# xmc.net
KiCad netlist of a schematic drawn in EAGLE
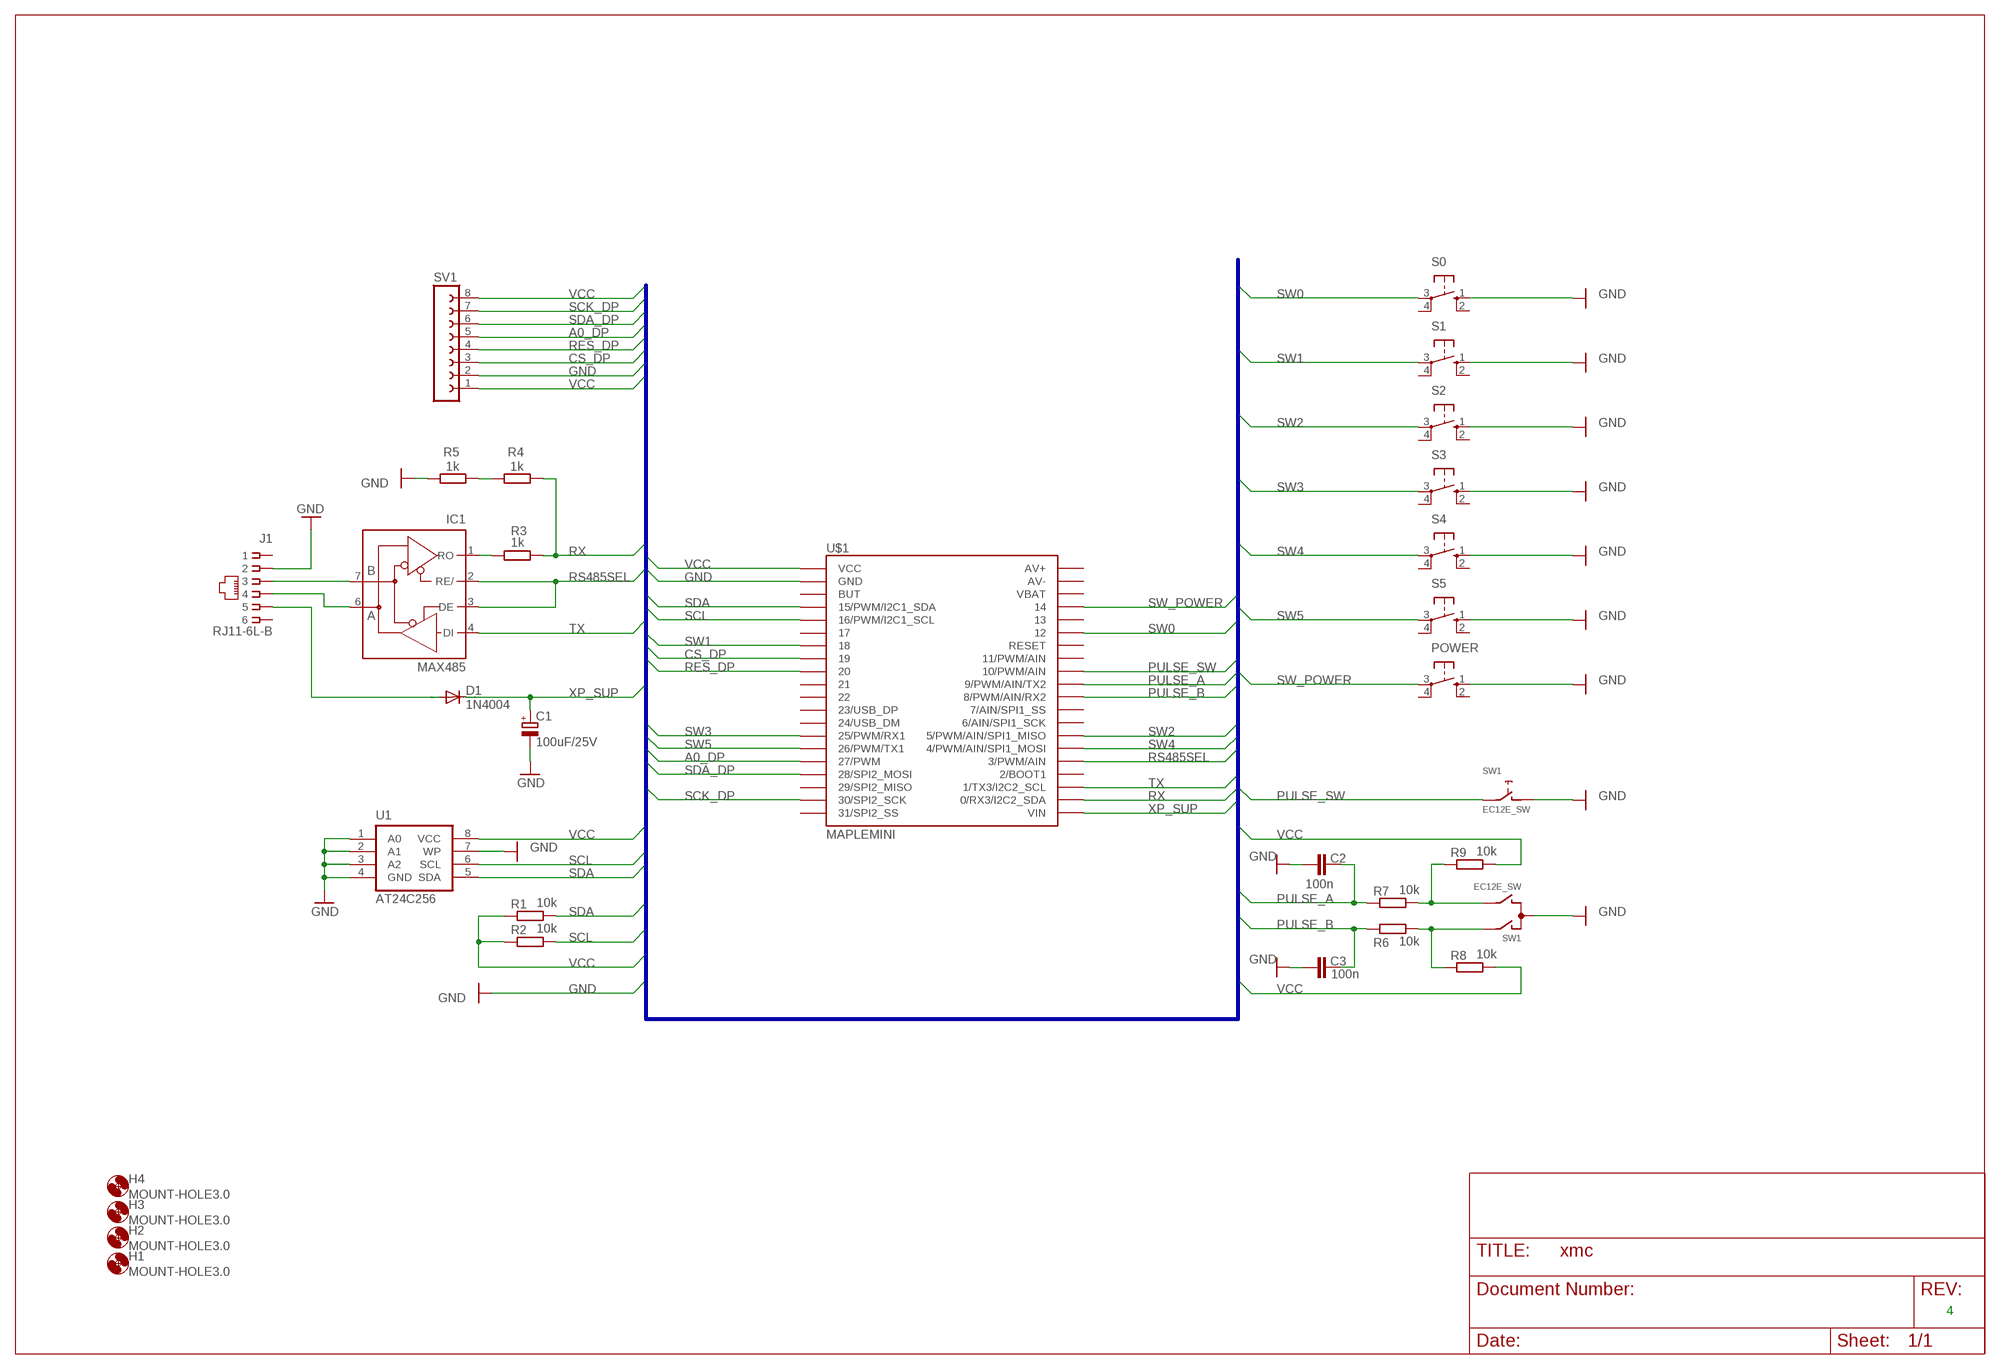
[diagram p0: schematic, sheet 1]

(export (version "E")
  (design (tool "Eeschema 10.0.6"))
  (components
    (comp (ref "C1")
      (value "100uF/25V")
      (footprint "eagle-import:E2,5-6")
      (libsource (lib "eagle-import") (part "CPOL-EUE2.5-6"))
    )
    (comp (ref "C2")
      (value "100n")
      (footprint "eagle-import:C025-024X044")
      (libsource (lib "eagle-import") (part "C-EU025-024X044"))
    )
    (comp (ref "C3")
      (value "100n")
      (footprint "eagle-import:C025-024X044")
      (libsource (lib "eagle-import") (part "C-EU025-024X044"))
    )
    (comp (ref "D1")
      (value "1N4004")
      (footprint "eagle-import:DO41-10")
      (libsource (lib "eagle-import") (part "1N4004"))
    )
    (comp (ref "H1")
      (value "MOUNT-HOLE3.0")
      (footprint "eagle-import:3,0")
      (libsource (lib "eagle-import") (part "MOUNT-HOLE3.0"))
    )
    (comp (ref "H2")
      (value "MOUNT-HOLE3.0")
      (footprint "eagle-import:3,0")
      (libsource (lib "eagle-import") (part "MOUNT-HOLE3.0"))
    )
    (comp (ref "H3")
      (value "MOUNT-HOLE3.0")
      (footprint "eagle-import:3,0")
      (libsource (lib "eagle-import") (part "MOUNT-HOLE3.0"))
    )
    (comp (ref "H4")
      (value "MOUNT-HOLE3.0")
      (footprint "eagle-import:3,0")
      (libsource (lib "eagle-import") (part "MOUNT-HOLE3.0"))
    )
    (comp (ref "IC1")
      (value "MAX485")
      (footprint "eagle-import:SO08")
      (fields (field (name "MF") "MAXIM") (field (name "MPN") "MAX481CSA"))
      (libsource (lib "eagle-import") (part "MAX481CSA"))
    )
    (comp (ref "J1")
      (value "RJ11-6L-B")
      (footprint "eagle-import:RJ11-NO_SHIELD")
      (fields (field (name "MF") "TYCO ELECTRONICS"))
      (libsource (lib "eagle-import") (part "RJ11-6L-B"))
    )
    (comp (ref "POWER")
      (value "10-XX")
      (footprint "eagle-import:B3F-10XX")
      (fields (field (name "MPN") "B3F-1000"))
      (libsource (lib "eagle-import") (part "10-XX"))
    )
    (comp (ref "R1")
      (value "10k")
      (footprint "eagle-import:0207_7")
      (libsource (lib "eagle-import") (part "R-EU_0207/7"))
    )
    (comp (ref "R2")
      (value "10k")
      (footprint "eagle-import:0207_7")
      (libsource (lib "eagle-import") (part "R-EU_0207/7"))
    )
    (comp (ref "R3")
      (value "1k")
      (footprint "eagle-import:0207_7")
      (libsource (lib "eagle-import") (part "R-EU_0207/7"))
    )
    (comp (ref "R4")
      (value "1k")
      (footprint "eagle-import:0207_7")
      (libsource (lib "eagle-import") (part "R-EU_0207/7"))
    )
    (comp (ref "R5")
      (value "1k")
      (footprint "eagle-import:0207_7")
      (libsource (lib "eagle-import") (part "R-EU_0207/7"))
    )
    (comp (ref "R6")
      (value "10k")
      (footprint "eagle-import:0207_7")
      (libsource (lib "eagle-import") (part "R-EU_0207/7"))
    )
    (comp (ref "R7")
      (value "10k")
      (footprint "eagle-import:0207_7")
      (libsource (lib "eagle-import") (part "R-EU_0207/7"))
    )
    (comp (ref "R8")
      (value "10k")
      (footprint "eagle-import:0207_7")
      (libsource (lib "eagle-import") (part "R-EU_0207/7"))
    )
    (comp (ref "R9")
      (value "10k")
      (footprint "eagle-import:0207_7")
      (libsource (lib "eagle-import") (part "R-EU_0207/7"))
    )
    (comp (ref "S0")
      (value "10-XX")
      (footprint "eagle-import:B3F-10XX")
      (fields (field (name "MPN") "B3F-1000"))
      (libsource (lib "eagle-import") (part "10-XX"))
    )
    (comp (ref "S1")
      (value "10-XX")
      (footprint "eagle-import:B3F-10XX")
      (fields (field (name "MPN") "B3F-1000"))
      (libsource (lib "eagle-import") (part "10-XX"))
    )
    (comp (ref "S2")
      (value "10-XX")
      (footprint "eagle-import:B3F-10XX")
      (fields (field (name "MPN") "B3F-1000"))
      (libsource (lib "eagle-import") (part "10-XX"))
    )
    (comp (ref "S3")
      (value "10-XX")
      (footprint "eagle-import:B3F-10XX")
      (fields (field (name "MPN") "B3F-1000"))
      (libsource (lib "eagle-import") (part "10-XX"))
    )
    (comp (ref "S4")
      (value "10-XX")
      (footprint "eagle-import:B3F-10XX")
      (fields (field (name "MPN") "B3F-1000"))
      (libsource (lib "eagle-import") (part "10-XX"))
    )
    (comp (ref "S5")
      (value "10-XX")
      (footprint "eagle-import:B3F-10XX")
      (fields (field (name "MPN") "B3F-1000"))
      (libsource (lib "eagle-import") (part "10-XX"))
    )
    (comp (ref "SV1")
      (value "FE08-1")
      (footprint "eagle-import:FE08")
      (libsource (lib "eagle-import") (part "FE08-1"))
    )
    (comp (ref "SW1")
      (value "EC12E_SW")
      (footprint "eagle-import:ALPS_EC12E_SW")
      (fields (field (name "MPN") "EC12E2424407"))
      (libsource (lib "eagle-import") (part "EC12E_SW"))
    )
    (comp (ref "U$1")
      (value "MAPLEMINI")
      (footprint "eagle-import:20-DIP")
      (libsource (lib "eagle-import") (part "MAPLEMINI"))
    )
    (comp (ref "U1")
      (value "AT24C256")
      (footprint "eagle-import:SO08-8S1")
      (libsource (lib "eagle-import") (part "AT24CXX"))
    )
  )
  (nets
    (net (code "1") (name "/A0_DP") (class "Default")
      (node (ref "SV1") (pin "5") (pinfunction "5_5") (pintype "passive"))
      (node (ref "U$1") (pin "16") (pinfunction "27/PWM_16") (pintype "bidirectional"))
    )
    (net (code "2") (name "/CS_DP") (class "Default")
      (node (ref "SV1") (pin "3") (pinfunction "3_3") (pintype "passive"))
      (node (ref "U$1") (pin "8") (pinfunction "19_8") (pintype "bidirectional"))
    )
    (net (code "3") (name "/PULSE_A") (class "Default")
      (node (ref "C2") (pin "1") (pinfunction "1_1") (pintype "passive"))
      (node (ref "R7") (pin "1") (pinfunction "1_1") (pintype "passive"))
      (node (ref "U$1") (pin "31") (pinfunction "9/PWM/AIN/TX2_31") (pintype "bidirectional"))
    )
    (net (code "4") (name "/PULSE_B") (class "Default")
      (node (ref "C3") (pin "1") (pinfunction "1_1") (pintype "passive"))
      (node (ref "R6") (pin "1") (pinfunction "1_1") (pintype "passive"))
      (node (ref "U$1") (pin "30") (pinfunction "8/PWM/AIN/RX2_30") (pintype "bidirectional"))
    )
    (net (code "5") (name "/PULSE_SW") (class "Default")
      (node (ref "SW1") (pin "E") (pinfunction "2_E") (pintype "passive"))
      (node (ref "U$1") (pin "32") (pinfunction "10/PWM/AIN_32") (pintype "bidirectional"))
    )
    (net (code "6") (name "/RES_DP") (class "Default")
      (node (ref "SV1") (pin "4") (pinfunction "4_4") (pintype "passive"))
      (node (ref "U$1") (pin "9") (pinfunction "20_9") (pintype "bidirectional"))
    )
    (net (code "7") (name "/RS485SEL") (class "Default")
      (node (ref "IC1") (pin "2") (pinfunction "RE/_2") (pintype "input"))
      (node (ref "IC1") (pin "3") (pinfunction "DE_3") (pintype "input"))
      (node (ref "U$1") (pin "25") (pinfunction "3/PWM/AIN_25") (pintype "bidirectional"))
    )
    (net (code "8") (name "/RX") (class "Default")
      (node (ref "R3") (pin "2") (pinfunction "2_2") (pintype "passive"))
      (node (ref "R4") (pin "1") (pinfunction "1_1") (pintype "passive"))
      (node (ref "U$1") (pin "22") (pinfunction "0/RX3/I2C2_SDA_22") (pintype "bidirectional"))
    )
    (net (code "9") (name "/SCK_DP") (class "Default")
      (node (ref "SV1") (pin "7") (pinfunction "7_7") (pintype "passive"))
      (node (ref "U$1") (pin "19") (pinfunction "30/SPI2_SCK_19") (pintype "bidirectional"))
    )
    (net (code "10") (name "/SCL") (class "Default")
      (node (ref "R2") (pin "2") (pinfunction "2_2") (pintype "passive"))
      (node (ref "U$1") (pin "5") (pinfunction "16/PWM/I2C1_SCL_5") (pintype "bidirectional"))
      (node (ref "U1") (pin "6") (pinfunction "SCL_6") (pintype "bidirectional"))
    )
    (net (code "11") (name "/SDA") (class "Default")
      (node (ref "R1") (pin "2") (pinfunction "2_2") (pintype "passive"))
      (node (ref "U$1") (pin "4") (pinfunction "15/PWM/I2C1_SDA_4") (pintype "bidirectional"))
      (node (ref "U1") (pin "5") (pinfunction "SDA_5") (pintype "bidirectional"))
    )
    (net (code "12") (name "/SDA_DP") (class "Default")
      (node (ref "SV1") (pin "6") (pinfunction "6_6") (pintype "passive"))
      (node (ref "U$1") (pin "17") (pinfunction "28/SPI2_MOSI_17") (pintype "bidirectional"))
    )
    (net (code "13") (name "/SW0") (class "Default")
      (node (ref "S0") (pin "3") (pinfunction "P_3") (pintype "passive"))
      (node (ref "U$1") (pin "35") (pinfunction "12_35") (pintype "bidirectional"))
    )
    (net (code "14") (name "/SW1") (class "Default")
      (node (ref "S1") (pin "3") (pinfunction "P_3") (pintype "passive"))
      (node (ref "U$1") (pin "7") (pinfunction "18_7") (pintype "bidirectional"))
    )
    (net (code "15") (name "/SW2") (class "Default")
      (node (ref "S2") (pin "3") (pinfunction "P_3") (pintype "passive"))
      (node (ref "U$1") (pin "27") (pinfunction "5/PWM/AIN/SPI1_MISO_27") (pintype "bidirectional"))
    )
    (net (code "16") (name "/SW3") (class "Default")
      (node (ref "S3") (pin "3") (pinfunction "P_3") (pintype "passive"))
      (node (ref "U$1") (pin "14") (pinfunction "25/PWM/RX1_14") (pintype "bidirectional"))
    )
    (net (code "17") (name "/SW4") (class "Default")
      (node (ref "S4") (pin "3") (pinfunction "P_3") (pintype "passive"))
      (node (ref "U$1") (pin "26") (pinfunction "4/PWM/AIN/SPI1_MOSI_26") (pintype "bidirectional"))
    )
    (net (code "18") (name "/SW5") (class "Default")
      (node (ref "S5") (pin "3") (pinfunction "P_3") (pintype "passive"))
      (node (ref "U$1") (pin "15") (pinfunction "26/PWM/TX1_15") (pintype "bidirectional"))
    )
    (net (code "19") (name "/SW_POWER") (class "Default")
      (node (ref "POWER") (pin "3") (pinfunction "P_3") (pintype "passive"))
      (node (ref "U$1") (pin "37") (pinfunction "14_37") (pintype "bidirectional"))
    )
    (net (code "20") (name "/TX") (class "Default")
      (node (ref "IC1") (pin "4") (pinfunction "DI_4") (pintype "input"))
      (node (ref "U$1") (pin "23") (pinfunction "1/TX3/I2C2_SCL_23") (pintype "bidirectional"))
    )
    (net (code "21") (name "/VCC") (class "Default")
      (node (ref "R1") (pin "1") (pinfunction "1_1") (pintype "passive"))
      (node (ref "R2") (pin "1") (pinfunction "1_1") (pintype "passive"))
      (node (ref "R8") (pin "2") (pinfunction "2_2") (pintype "passive"))
      (node (ref "R9") (pin "2") (pinfunction "2_2") (pintype "passive"))
      (node (ref "SV1") (pin "1") (pinfunction "1_1") (pintype "passive"))
      (node (ref "SV1") (pin "8") (pinfunction "8_8") (pintype "passive"))
      (node (ref "U$1") (pin "1") (pinfunction "VCC_1") (pintype "bidirectional"))
      (node (ref "U1") (pin "8") (pinfunction "VCC_8") (pintype "power_in"))
    )
    (net (code "22") (name "/XP_SUP") (class "Default")
      (node (ref "C1") (pin "+") (pinfunction "+_+") (pintype "passive"))
      (node (ref "D1") (pin "C") (pinfunction "C_C") (pintype "passive"))
      (node (ref "U$1") (pin "21") (pinfunction "VIN_21") (pintype "bidirectional"))
    )
    (net (code "23") (name "GND") (class "Default")
      (node (ref "C1") (pin "-") (pinfunction "-_-") (pintype "passive"))
      (node (ref "C2") (pin "2") (pinfunction "2_2") (pintype "passive"))
      (node (ref "C3") (pin "2") (pinfunction "2_2") (pintype "passive"))
      (node (ref "J1") (pin "2") (pinfunction "2_2") (pintype "passive"))
      (node (ref "POWER") (pin "1") (pinfunction "S_1") (pintype "passive"))
      (node (ref "R5") (pin "2") (pinfunction "2_2") (pintype "passive"))
      (node (ref "S0") (pin "1") (pinfunction "S_1") (pintype "passive"))
      (node (ref "S1") (pin "1") (pinfunction "S_1") (pintype "passive"))
      (node (ref "S2") (pin "1") (pinfunction "S_1") (pintype "passive"))
      (node (ref "S3") (pin "1") (pinfunction "S_1") (pintype "passive"))
      (node (ref "S4") (pin "1") (pinfunction "S_1") (pintype "passive"))
      (node (ref "S5") (pin "1") (pinfunction "S_1") (pintype "passive"))
      (node (ref "SV1") (pin "2") (pinfunction "2_2") (pintype "passive"))
      (node (ref "SW1") (pin "C") (pinfunction "C_C") (pintype "passive"))
      (node (ref "SW1") (pin "D") (pinfunction "1_D") (pintype "passive"))
      (node (ref "U$1") (pin "2") (pinfunction "GND_2") (pintype "bidirectional"))
      (node (ref "U1") (pin "1") (pinfunction "A0_1") (pintype "input"))
      (node (ref "U1") (pin "2") (pinfunction "A1_2") (pintype "input"))
      (node (ref "U1") (pin "3") (pinfunction "A2_3") (pintype "input"))
      (node (ref "U1") (pin "4") (pinfunction "GND_4") (pintype "power_in"))
      (node (ref "U1") (pin "7") (pinfunction "WP_7") (pintype "bidirectional"))
    )
    (net (code "24") (name "Net-(D1-PadA)") (class "Default")
      (node (ref "D1") (pin "A") (pinfunction "A_A") (pintype "passive"))
      (node (ref "J1") (pin "5") (pinfunction "5_5") (pintype "passive"))
    )
    (net (code "25") (name "Net-(IC1A-A)") (class "Default")
      (node (ref "IC1") (pin "6") (pinfunction "A_6") (pintype "passive"))
      (node (ref "J1") (pin "4") (pinfunction "4_4") (pintype "passive"))
    )
    (net (code "26") (name "Net-(IC1A-B)") (class "Default")
      (node (ref "IC1") (pin "7") (pinfunction "B_7") (pintype "passive"))
      (node (ref "J1") (pin "3") (pinfunction "3_3") (pintype "passive"))
    )
    (net (code "27") (name "Net-(IC1A-RO)") (class "Default")
      (node (ref "IC1") (pin "1") (pinfunction "RO_1") (pintype "output"))
      (node (ref "R3") (pin "1") (pinfunction "1_1") (pintype "passive"))
    )
    (net (code "28") (name "Net-(R4-Pad2)") (class "Default")
      (node (ref "R4") (pin "2") (pinfunction "2_2") (pintype "passive"))
      (node (ref "R5") (pin "1") (pinfunction "1_1") (pintype "passive"))
    )
    (net (code "29") (name "Net-(R6-Pad2)") (class "Default")
      (node (ref "R6") (pin "2") (pinfunction "2_2") (pintype "passive"))
      (node (ref "R8") (pin "1") (pinfunction "1_1") (pintype "passive"))
      (node (ref "SW1") (pin "A") (pinfunction "A_A") (pintype "passive"))
    )
    (net (code "30") (name "Net-(R7-Pad2)") (class "Default")
      (node (ref "R7") (pin "2") (pinfunction "2_2") (pintype "passive"))
      (node (ref "R9") (pin "1") (pinfunction "1_1") (pintype "passive"))
      (node (ref "SW1") (pin "B") (pinfunction "B_B") (pintype "passive"))
    )
    (net (code "31") (name "unconnected-(J1-Pad1)") (class "Default")
      (node (ref "J1") (pin "1") (pinfunction "1_1") (pintype "passive"))
    )
    (net (code "32") (name "unconnected-(J1-Pad6)") (class "Default")
      (node (ref "J1") (pin "6") (pinfunction "6_6") (pintype "passive"))
    )
    (net (code "33") (name "unconnected-(POWER-P1-Pad4)") (class "Default")
      (node (ref "POWER") (pin "4") (pinfunction "P1_4") (pintype "passive"))
    )
    (net (code "34") (name "unconnected-(POWER-S1-Pad2)") (class "Default")
      (node (ref "POWER") (pin "2") (pinfunction "S1_2") (pintype "passive"))
    )
    (net (code "35") (name "unconnected-(S0-P1-Pad4)") (class "Default")
      (node (ref "S0") (pin "4") (pinfunction "P1_4") (pintype "passive"))
    )
    (net (code "36") (name "unconnected-(S0-S1-Pad2)") (class "Default")
      (node (ref "S0") (pin "2") (pinfunction "S1_2") (pintype "passive"))
    )
    (net (code "37") (name "unconnected-(S1-P1-Pad4)") (class "Default")
      (node (ref "S1") (pin "4") (pinfunction "P1_4") (pintype "passive"))
    )
    (net (code "38") (name "unconnected-(S1-S1-Pad2)") (class "Default")
      (node (ref "S1") (pin "2") (pinfunction "S1_2") (pintype "passive"))
    )
    (net (code "39") (name "unconnected-(S2-P1-Pad4)") (class "Default")
      (node (ref "S2") (pin "4") (pinfunction "P1_4") (pintype "passive"))
    )
    (net (code "40") (name "unconnected-(S2-S1-Pad2)") (class "Default")
      (node (ref "S2") (pin "2") (pinfunction "S1_2") (pintype "passive"))
    )
    (net (code "41") (name "unconnected-(S3-P1-Pad4)") (class "Default")
      (node (ref "S3") (pin "4") (pinfunction "P1_4") (pintype "passive"))
    )
    (net (code "42") (name "unconnected-(S3-S1-Pad2)") (class "Default")
      (node (ref "S3") (pin "2") (pinfunction "S1_2") (pintype "passive"))
    )
    (net (code "43") (name "unconnected-(S4-P1-Pad4)") (class "Default")
      (node (ref "S4") (pin "4") (pinfunction "P1_4") (pintype "passive"))
    )
    (net (code "44") (name "unconnected-(S4-S1-Pad2)") (class "Default")
      (node (ref "S4") (pin "2") (pinfunction "S1_2") (pintype "passive"))
    )
    (net (code "45") (name "unconnected-(S5-P1-Pad4)") (class "Default")
      (node (ref "S5") (pin "4") (pinfunction "P1_4") (pintype "passive"))
    )
    (net (code "46") (name "unconnected-(S5-S1-Pad2)") (class "Default")
      (node (ref "S5") (pin "2") (pinfunction "S1_2") (pintype "passive"))
    )
    (net (code "47") (name "unconnected-(U$1-2{slash}BOOT1-Pad24)") (class "Default")
      (node (ref "U$1") (pin "24") (pinfunction "2/BOOT1_24") (pintype "bidirectional"))
    )
    (net (code "48") (name "unconnected-(U$1-6{slash}AIN{slash}SPI1_SCK-Pad28)") (class "Default")
      (node (ref "U$1") (pin "28") (pinfunction "6/AIN/SPI1_SCK_28") (pintype "bidirectional"))
    )
    (net (code "49") (name "unconnected-(U$1-7{slash}AIN{slash}SPI1_SS-Pad29)") (class "Default")
      (node (ref "U$1") (pin "29") (pinfunction "7/AIN/SPI1_SS_29") (pintype "bidirectional"))
    )
    (net (code "50") (name "unconnected-(U$1-11{slash}PWM{slash}AIN-Pad33)") (class "Default")
      (node (ref "U$1") (pin "33") (pinfunction "11/PWM/AIN_33") (pintype "bidirectional"))
    )
    (net (code "51") (name "unconnected-(U$1-13-Pad36)") (class "Default")
      (node (ref "U$1") (pin "36") (pinfunction "13_36") (pintype "bidirectional"))
    )
    (net (code "52") (name "unconnected-(U$1-17-Pad6)") (class "Default")
      (node (ref "U$1") (pin "6") (pinfunction "17_6") (pintype "bidirectional"))
    )
    (net (code "53") (name "unconnected-(U$1-21-Pad10)") (class "Default")
      (node (ref "U$1") (pin "10") (pinfunction "21_10") (pintype "bidirectional"))
    )
    (net (code "54") (name "unconnected-(U$1-22-Pad11)") (class "Default")
      (node (ref "U$1") (pin "11") (pinfunction "22_11") (pintype "bidirectional"))
    )
    (net (code "55") (name "unconnected-(U$1-23{slash}USB_DP-Pad12)") (class "Default")
      (node (ref "U$1") (pin "12") (pinfunction "23/USB_DP_12") (pintype "bidirectional"))
    )
    (net (code "56") (name "unconnected-(U$1-24{slash}USB_DM-Pad13)") (class "Default")
      (node (ref "U$1") (pin "13") (pinfunction "24/USB_DM_13") (pintype "bidirectional"))
    )
    (net (code "57") (name "unconnected-(U$1-29{slash}SPI2_MISO-Pad18)") (class "Default")
      (node (ref "U$1") (pin "18") (pinfunction "29/SPI2_MISO_18") (pintype "bidirectional"))
    )
    (net (code "58") (name "unconnected-(U$1-31{slash}SPI2_SS-Pad20)") (class "Default")
      (node (ref "U$1") (pin "20") (pinfunction "31/SPI2_SS_20") (pintype "bidirectional"))
    )
    (net (code "59") (name "unconnected-(U$1-AV+-Pad40)") (class "Default")
      (node (ref "U$1") (pin "40") (pinfunction "AV+_40") (pintype "bidirectional"))
    )
    (net (code "60") (name "unconnected-(U$1-AV--Pad39)") (class "Default")
      (node (ref "U$1") (pin "39") (pinfunction "AV-_39") (pintype "bidirectional"))
    )
    (net (code "61") (name "unconnected-(U$1-BUT-Pad3)") (class "Default")
      (node (ref "U$1") (pin "3") (pinfunction "BUT_3") (pintype "bidirectional"))
    )
    (net (code "62") (name "unconnected-(U$1-RESET-Pad34)") (class "Default")
      (node (ref "U$1") (pin "34") (pinfunction "RESET_34") (pintype "bidirectional"))
    )
    (net (code "63") (name "unconnected-(U$1-VBAT-Pad38)") (class "Default")
      (node (ref "U$1") (pin "38") (pinfunction "VBAT_38") (pintype "bidirectional"))
    )
  )
)
